# watering_board.net
KiCad netlist of a schematic drawn in EAGLE
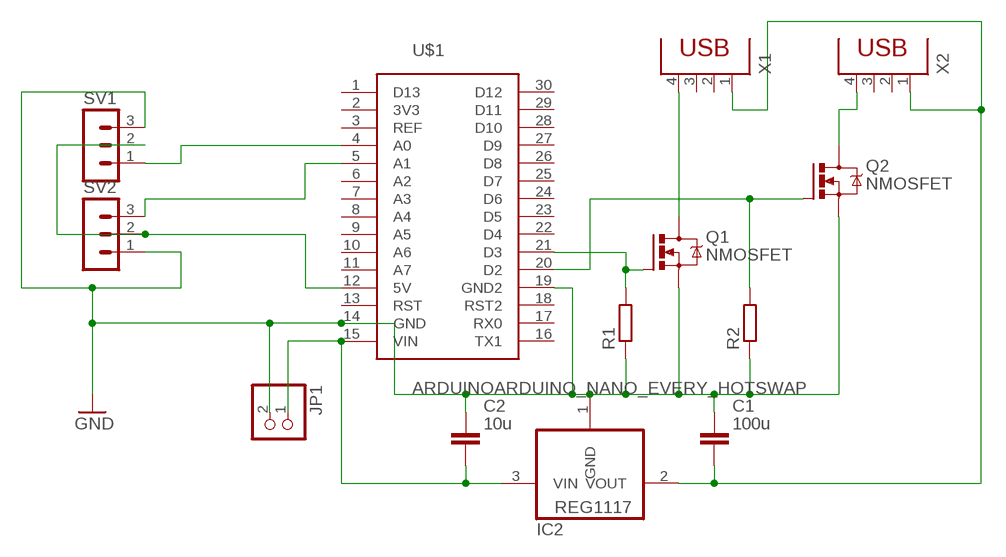
[diagram p0: schematic, sheet 1]

(export (version "E")
  (design (tool "Eeschema 10.0.6"))
  (components
    (comp (ref "C1")
      (value "100u")
      (footprint "eagle-import:CAPC3216X135")
      (libsource (lib "eagle-import") (part "CCHIP-1206(3216-METRIC)_"))
    )
    (comp (ref "C2")
      (value "10u")
      (footprint "eagle-import:CAPC3216X135")
      (libsource (lib "eagle-import") (part "CCHIP-1206(3216-METRIC)_"))
    )
    (comp (ref "IC2")
      (value "REG1117")
      (footprint "eagle-import:SOT223")
      (libsource (lib "eagle-import") (part "REG1117"))
    )
    (comp (ref "JP1")
      (value "PINHD-1X2")
      (footprint "eagle-import:1X02")
      (libsource (lib "eagle-import") (part "PINHD-1X2"))
    )
    (comp (ref "Q1")
      (value "NMOSFET")
      (footprint "eagle-import:SOT23")
      (libsource (lib "eagle-import") (part "NMOSFETSOT23"))
    )
    (comp (ref "Q2")
      (value "NMOSFET")
      (footprint "eagle-import:SOT23")
      (libsource (lib "eagle-import") (part "NMOSFETSOT23"))
    )
    (comp (ref "R1")
      (value "R-EU_M1206")
      (footprint "eagle-import:M1206")
      (libsource (lib "eagle-import") (part "R-EU_M1206"))
    )
    (comp (ref "R2")
      (value "R-EU_M1206")
      (footprint "eagle-import:M1206")
      (libsource (lib "eagle-import") (part "R-EU_M1206"))
    )
    (comp (ref "SV1")
      (value "MA03-1")
      (footprint "eagle-import:MA03-1")
      (libsource (lib "eagle-import") (part "MA03-1"))
    )
    (comp (ref "SV2")
      (value "MA03-1")
      (footprint "eagle-import:MA03-1")
      (libsource (lib "eagle-import") (part "MA03-1"))
    )
    (comp (ref "U$1")
      (value "ARDUINOARDUINO_NANO_EVERY_HOTSWAP")
      (footprint "eagle-import:DIP1524W80P254L4318H508Q30B")
      (libsource (lib "eagle-import") (part "ARDUINOARDUINO_NANO_EVERY_HOTSWAP"))
    )
    (comp (ref "X1")
      (value "PN87520")
      (footprint "eagle-import:PN87520")
      (libsource (lib "eagle-import") (part "PN87520"))
    )
    (comp (ref "X2")
      (value "PN87520")
      (footprint "eagle-import:PN87520")
      (libsource (lib "eagle-import") (part "PN87520"))
    )
  )
  (nets
    (net (code "1") (name "/3V3") (class "Default")
      (node (ref "U$1") (pin "2") (pinfunction "3V3_2") (pintype "power_in"))
    )
    (net (code "2") (name "GND") (class "Default")
      (node (ref "C1") (pin "1") (pinfunction "1_1") (pintype "passive"))
      (node (ref "C2") (pin "1") (pinfunction "1_1") (pintype "passive"))
      (node (ref "IC2") (pin "1") (pinfunction "GND_1") (pintype "power_in"))
      (node (ref "JP1") (pin "2") (pinfunction "2_2") (pintype "passive"))
      (node (ref "Q1") (pin "2") (pinfunction "S_2") (pintype "passive"))
      (node (ref "Q2") (pin "2") (pinfunction "S_2") (pintype "passive"))
      (node (ref "R1") (pin "1") (pinfunction "1_1") (pintype "passive"))
      (node (ref "R2") (pin "1") (pinfunction "1_1") (pintype "passive"))
      (node (ref "SV1") (pin "3") (pinfunction "3_3") (pintype "passive"))
      (node (ref "SV2") (pin "1") (pinfunction "1_1") (pintype "passive"))
      (node (ref "U$1") (pin "14") (pinfunction "GND_14") (pintype "power_in"))
      (node (ref "U$1") (pin "19") (pinfunction "GND2_19") (pintype "power_in"))
    )
    (net (code "3") (name "Net-(IC2-VIN)") (class "Default")
      (node (ref "C2") (pin "2") (pinfunction "2_2") (pintype "passive"))
      (node (ref "IC2") (pin "3") (pinfunction "VIN_3") (pintype "input"))
      (node (ref "JP1") (pin "1") (pinfunction "1_1") (pintype "passive"))
      (node (ref "U$1") (pin "15") (pinfunction "VIN_15") (pintype "power_in"))
    )
    (net (code "4") (name "Net-(IC2-VOUT)") (class "Default")
      (node (ref "C1") (pin "2") (pinfunction "2_2") (pintype "passive"))
      (node (ref "IC2") (pin "2") (pinfunction "VOUT_2") (pintype "output"))
      (node (ref "X1") (pin "1") (pinfunction "1_1") (pintype "passive"))
      (node (ref "X2") (pin "1") (pinfunction "1_1") (pintype "passive"))
    )
    (net (code "5") (name "Net-(Q1-D)") (class "Default")
      (node (ref "Q1") (pin "3") (pinfunction "D_3") (pintype "passive"))
      (node (ref "X1") (pin "4") (pinfunction "4_4") (pintype "passive"))
    )
    (net (code "6") (name "Net-(Q1-G)") (class "Default")
      (node (ref "Q1") (pin "1") (pinfunction "G_1") (pintype "passive"))
      (node (ref "R1") (pin "2") (pinfunction "2_2") (pintype "passive"))
      (node (ref "U$1") (pin "21") (pinfunction "D3_21") (pintype "bidirectional"))
    )
    (net (code "7") (name "Net-(Q2-D)") (class "Default")
      (node (ref "Q2") (pin "3") (pinfunction "D_3") (pintype "passive"))
      (node (ref "X2") (pin "4") (pinfunction "4_4") (pintype "passive"))
    )
    (net (code "8") (name "Net-(Q2-G)") (class "Default")
      (node (ref "Q2") (pin "1") (pinfunction "G_1") (pintype "passive"))
      (node (ref "R2") (pin "2") (pinfunction "2_2") (pintype "passive"))
      (node (ref "U$1") (pin "20") (pinfunction "D2_20") (pintype "bidirectional"))
    )
    (net (code "9") (name "Net-(U$1-5V)") (class "Default")
      (node (ref "SV1") (pin "2") (pinfunction "2_2") (pintype "passive"))
      (node (ref "SV2") (pin "2") (pinfunction "2_2") (pintype "passive"))
      (node (ref "U$1") (pin "12") (pinfunction "5V_12") (pintype "power_in"))
    )
    (net (code "10") (name "Net-(U$1-A0)") (class "Default")
      (node (ref "SV1") (pin "1") (pinfunction "1_1") (pintype "passive"))
      (node (ref "U$1") (pin "4") (pinfunction "A0_4") (pintype "bidirectional"))
    )
    (net (code "11") (name "Net-(U$1-A1)") (class "Default")
      (node (ref "SV2") (pin "3") (pinfunction "3_3") (pintype "passive"))
      (node (ref "U$1") (pin "5") (pinfunction "A1_5") (pintype "bidirectional"))
    )
    (net (code "12") (name "unconnected-(U$1-A2-Pad6)") (class "Default")
      (node (ref "U$1") (pin "6") (pinfunction "A2_6") (pintype "bidirectional"))
    )
    (net (code "13") (name "unconnected-(U$1-A3-Pad7)") (class "Default")
      (node (ref "U$1") (pin "7") (pinfunction "A3_7") (pintype "bidirectional"))
    )
    (net (code "14") (name "unconnected-(U$1-A4-Pad8)") (class "Default")
      (node (ref "U$1") (pin "8") (pinfunction "A4_8") (pintype "bidirectional"))
    )
    (net (code "15") (name "unconnected-(U$1-A5-Pad9)") (class "Default")
      (node (ref "U$1") (pin "9") (pinfunction "A5_9") (pintype "bidirectional"))
    )
    (net (code "16") (name "unconnected-(U$1-A6-Pad10)") (class "Default")
      (node (ref "U$1") (pin "10") (pinfunction "A6_10") (pintype "bidirectional"))
    )
    (net (code "17") (name "unconnected-(U$1-A7-Pad11)") (class "Default")
      (node (ref "U$1") (pin "11") (pinfunction "A7_11") (pintype "bidirectional"))
    )
    (net (code "18") (name "unconnected-(U$1-D4-Pad22)") (class "Default")
      (node (ref "U$1") (pin "22") (pinfunction "D4_22") (pintype "bidirectional"))
    )
    (net (code "19") (name "unconnected-(U$1-D5-Pad23)") (class "Default")
      (node (ref "U$1") (pin "23") (pinfunction "D5_23") (pintype "bidirectional"))
    )
    (net (code "20") (name "unconnected-(U$1-D6-Pad24)") (class "Default")
      (node (ref "U$1") (pin "24") (pinfunction "D6_24") (pintype "bidirectional"))
    )
    (net (code "21") (name "unconnected-(U$1-D7-Pad25)") (class "Default")
      (node (ref "U$1") (pin "25") (pinfunction "D7_25") (pintype "bidirectional"))
    )
    (net (code "22") (name "unconnected-(U$1-D8-Pad26)") (class "Default")
      (node (ref "U$1") (pin "26") (pinfunction "D8_26") (pintype "bidirectional"))
    )
    (net (code "23") (name "unconnected-(U$1-D9-Pad27)") (class "Default")
      (node (ref "U$1") (pin "27") (pinfunction "D9_27") (pintype "bidirectional"))
    )
    (net (code "24") (name "unconnected-(U$1-D10-Pad28)") (class "Default")
      (node (ref "U$1") (pin "28") (pinfunction "D10_28") (pintype "bidirectional"))
    )
    (net (code "25") (name "unconnected-(U$1-D11-Pad29)") (class "Default")
      (node (ref "U$1") (pin "29") (pinfunction "D11_29") (pintype "bidirectional"))
    )
    (net (code "26") (name "unconnected-(U$1-D12-Pad30)") (class "Default")
      (node (ref "U$1") (pin "30") (pinfunction "D12_30") (pintype "bidirectional"))
    )
    (net (code "27") (name "unconnected-(U$1-D13-Pad1)") (class "Default")
      (node (ref "U$1") (pin "1") (pinfunction "D13_1") (pintype "bidirectional"))
    )
    (net (code "28") (name "unconnected-(U$1-REF-Pad3)") (class "Default")
      (node (ref "U$1") (pin "3") (pinfunction "REF_3") (pintype "bidirectional"))
    )
    (net (code "29") (name "unconnected-(U$1-RST-Pad13)") (class "Default")
      (node (ref "U$1") (pin "13") (pinfunction "RST_13") (pintype "input"))
    )
    (net (code "30") (name "unconnected-(U$1-RST2-Pad18)") (class "Default")
      (node (ref "U$1") (pin "18") (pinfunction "RST2_18") (pintype "input"))
    )
    (net (code "31") (name "unconnected-(U$1-RX0-Pad17)") (class "Default")
      (node (ref "U$1") (pin "17") (pinfunction "RX0_17") (pintype "input"))
    )
    (net (code "32") (name "unconnected-(U$1-TX1-Pad16)") (class "Default")
      (node (ref "U$1") (pin "16") (pinfunction "TX1_16") (pintype "output"))
    )
    (net (code "33") (name "unconnected-(X1-Pad2)") (class "Default")
      (node (ref "X1") (pin "2") (pinfunction "2_2") (pintype "passive"))
    )
    (net (code "34") (name "unconnected-(X1-Pad3)") (class "Default")
      (node (ref "X1") (pin "3") (pinfunction "3_3") (pintype "passive"))
    )
    (net (code "35") (name "unconnected-(X2-Pad2)") (class "Default")
      (node (ref "X2") (pin "2") (pinfunction "2_2") (pintype "passive"))
    )
    (net (code "36") (name "unconnected-(X2-Pad3)") (class "Default")
      (node (ref "X2") (pin "3") (pinfunction "3_3") (pintype "passive"))
    )
  )
)
